# waterius-factory-2_0.net
KiCad netlist of a schematic drawn in EAGLE
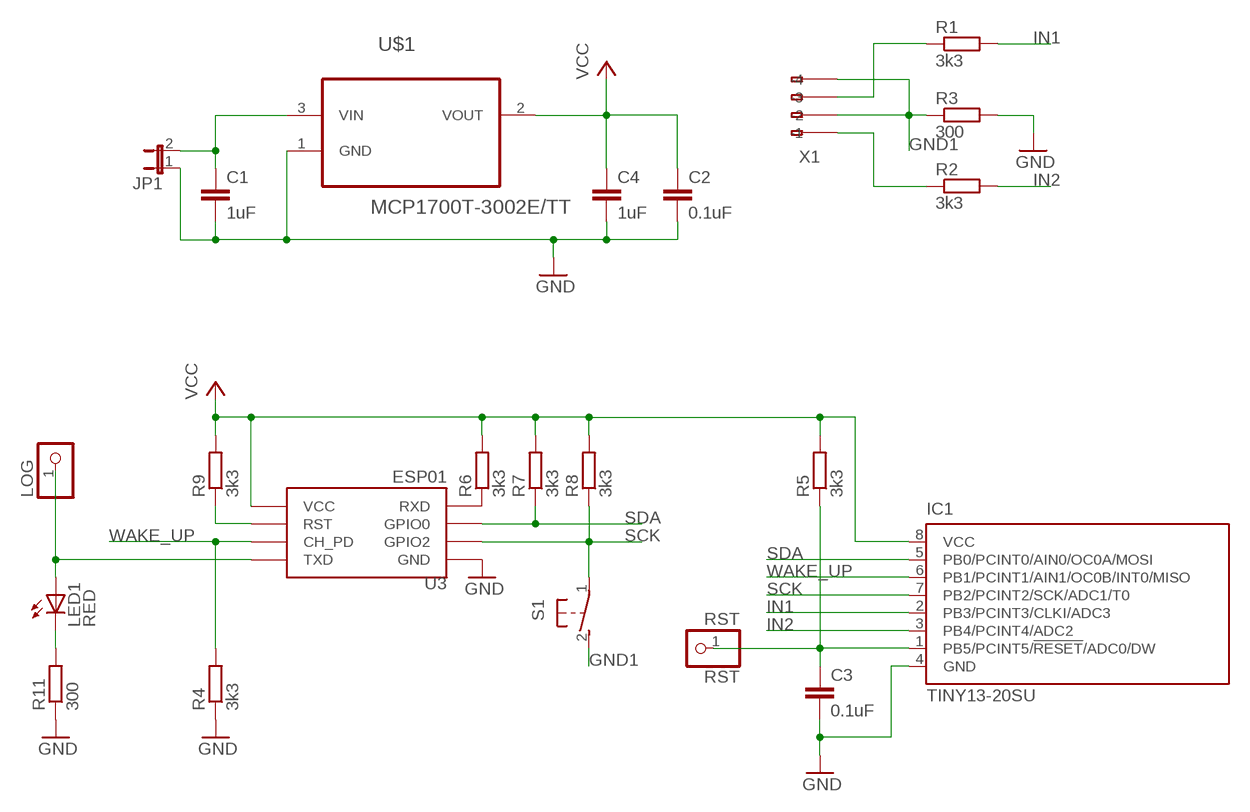
[diagram p0: schematic, sheet 1]

(export (version "E")
  (design (tool "Eeschema 10.0.6"))
  (components
    (comp (ref "C1")
      (value "1uF")
      (footprint "eagle-import:C0805")
      (libsource (lib "eagle-import") (part "C-EUC0805"))
    )
    (comp (ref "C2")
      (value "0.1uF")
      (footprint "eagle-import:C0805")
      (libsource (lib "eagle-import") (part "C-EUC0805"))
    )
    (comp (ref "C3")
      (value "0.1uF")
      (footprint "eagle-import:C0805")
      (libsource (lib "eagle-import") (part "C-EUC0805"))
    )
    (comp (ref "C4")
      (value "1uF")
      (footprint "eagle-import:C0805")
      (libsource (lib "eagle-import") (part "C-EUC0805"))
    )
    (comp (ref "IC1")
      (value "TINY13-20SU")
      (footprint "eagle-import:8S2")
      (fields (field (name "MPN") "ATTINY13-20SU"))
      (libsource (lib "eagle-import") (part "TINY13SU-20"))
    )
    (comp (ref "JP1")
      (value "JP1E")
      (footprint "eagle-import:JP1")
      (libsource (lib "eagle-import") (part "JP1E"))
    )
    (comp (ref "LED1")
      (value "RED")
      (footprint "eagle-import:LED3MM")
      (libsource (lib "eagle-import") (part "LED3MM"))
    )
    (comp (ref "LOG")
      (value "PINHD-1X1")
      (footprint "eagle-import:1X01")
      (libsource (lib "eagle-import") (part "PINHD-1X1"))
    )
    (comp (ref "R1")
      (value "3k3")
      (footprint "eagle-import:R0805")
      (libsource (lib "eagle-import") (part "R-EU_R0805"))
    )
    (comp (ref "R2")
      (value "3k3")
      (footprint "eagle-import:R0805")
      (libsource (lib "eagle-import") (part "R-EU_R0805"))
    )
    (comp (ref "R3")
      (value "300")
      (footprint "eagle-import:R0805")
      (libsource (lib "eagle-import") (part "R-EU_R0805"))
    )
    (comp (ref "R4")
      (value "3k3")
      (footprint "eagle-import:R0805")
      (libsource (lib "eagle-import") (part "R-EU_R0805"))
    )
    (comp (ref "R5")
      (value "3k3")
      (footprint "eagle-import:R0805")
      (libsource (lib "eagle-import") (part "R-EU_R0805"))
    )
    (comp (ref "R6")
      (value "3k3")
      (footprint "eagle-import:R0805")
      (libsource (lib "eagle-import") (part "R-EU_R0805"))
    )
    (comp (ref "R7")
      (value "3k3")
      (footprint "eagle-import:R0805")
      (libsource (lib "eagle-import") (part "R-EU_R0805"))
    )
    (comp (ref "R8")
      (value "3k3")
      (footprint "eagle-import:R0805")
      (libsource (lib "eagle-import") (part "R-EU_R0805"))
    )
    (comp (ref "R9")
      (value "3k3")
      (footprint "eagle-import:R0805")
      (libsource (lib "eagle-import") (part "R-EU_R0805"))
    )
    (comp (ref "R11")
      (value "300")
      (footprint "eagle-import:R0805")
      (libsource (lib "eagle-import") (part "R-EU_R0805"))
    )
    (comp (ref "RST")
      (value "RST")
      (footprint "eagle-import:1X01")
      (libsource (lib "eagle-import") (part "PINHD-1X1"))
    )
    (comp (ref "S1")
      (value "31-XX")
      (footprint "eagle-import:B3F-31XX")
      (fields (field (name "MPN") "B3F-3100"))
      (libsource (lib "eagle-import") (part "31-XX"))
    )
    (comp (ref "U$1")
      (value "MCP1700T-3002E/TT")
      (footprint "eagle-import:SOT95P237X112-3N")
      (fields (field (name "MF") "Microchip"))
      (libsource (lib "eagle-import") (part "MCP1700T-3002E/TT"))
    )
    (comp (ref "U3")
      (value "ESP01")
      (footprint "eagle-import:ESP01")
      (libsource (lib "eagle-import") (part "ESP01"))
    )
    (comp (ref "X1")
      (value "233-104")
      (footprint "eagle-import:233-104")
      (libsource (lib "eagle-import") (part "233-104"))
    )
  )
  (nets
    (net (code "1") (name "/GND1") (class "Default")
      (node (ref "R3") (pin "1") (pinfunction "1_1") (pintype "passive"))
      (node (ref "S1") (pin "2") (pinfunction "S_2") (pintype "passive"))
      (node (ref "X1") (pin "A2") (pinfunction "-2_A2") (pintype "passive"))
      (node (ref "X1") (pin "A4") (pinfunction "-4_A4") (pintype "passive"))
    )
    (net (code "2") (name "/IN1") (class "Default")
      (node (ref "IC1") (pin "2") (pinfunction "PB3/PCINT3/CLKI/ADC3_2") (pintype "bidirectional"))
      (node (ref "R1") (pin "2") (pinfunction "2_2") (pintype "passive"))
    )
    (net (code "3") (name "/IN2") (class "Default")
      (node (ref "IC1") (pin "3") (pinfunction "PB4/PCINT4/ADC2_3") (pintype "bidirectional"))
      (node (ref "R2") (pin "2") (pinfunction "2_2") (pintype "passive"))
    )
    (net (code "4") (name "/SCK") (class "Default")
      (node (ref "IC1") (pin "7") (pinfunction "PB2/PCINT2/SCK/ADC1/T0_7") (pintype "bidirectional"))
      (node (ref "R8") (pin "1") (pinfunction "1_1") (pintype "passive"))
      (node (ref "S1") (pin "1") (pinfunction "P_1") (pintype "passive"))
      (node (ref "U3") (pin "GPIO2") (pinfunction "GPIO2_GPIO2") (pintype "bidirectional"))
    )
    (net (code "5") (name "/SDA") (class "Default")
      (node (ref "IC1") (pin "5") (pinfunction "PB0/PCINT0/AIN0/OC0A/MOSI_5") (pintype "bidirectional"))
      (node (ref "R7") (pin "1") (pinfunction "1_1") (pintype "passive"))
      (node (ref "U3") (pin "GPIO0") (pinfunction "GPIO0_GPIO0") (pintype "bidirectional"))
    )
    (net (code "6") (name "/WAKE_UP") (class "Default")
      (node (ref "IC1") (pin "6") (pinfunction "PB1/PCINT1/AIN1/OC0B/INT0/MISO_6") (pintype "bidirectional"))
      (node (ref "R4") (pin "2") (pinfunction "2_2") (pintype "passive"))
      (node (ref "U3") (pin "CH_PD") (pinfunction "CH_PD_CH_PD") (pintype "bidirectional"))
    )
    (net (code "7") (name "GND") (class "Default")
      (node (ref "C1") (pin "2") (pinfunction "2_2") (pintype "passive"))
      (node (ref "C2") (pin "2") (pinfunction "2_2") (pintype "passive"))
      (node (ref "C3") (pin "2") (pinfunction "2_2") (pintype "passive"))
      (node (ref "C4") (pin "2") (pinfunction "2_2") (pintype "passive"))
      (node (ref "IC1") (pin "4") (pinfunction "GND_4") (pintype "power_in"))
      (node (ref "JP1") (pin "1") (pinfunction "1_1") (pintype "passive"))
      (node (ref "R11") (pin "1") (pinfunction "1_1") (pintype "passive"))
      (node (ref "R3") (pin "2") (pinfunction "2_2") (pintype "passive"))
      (node (ref "R4") (pin "1") (pinfunction "1_1") (pintype "passive"))
      (node (ref "U$1") (pin "1") (pinfunction "GND_1") (pintype "passive"))
      (node (ref "U3") (pin "GND") (pinfunction "GND_GND") (pintype "bidirectional"))
    )
    (net (code "8") (name "Net-(IC1-PB5{slash}PCINT5{slash}~{RESET}{slash}ADC0{slash}DW)") (class "Default")
      (node (ref "C3") (pin "1") (pinfunction "1_1") (pintype "passive"))
      (node (ref "IC1") (pin "1") (pinfunction "PB5/PCINT5/~{RESET}/ADC0/DW_1") (pintype "bidirectional"))
      (node (ref "R5") (pin "1") (pinfunction "1_1") (pintype "passive"))
      (node (ref "RST") (pin "1") (pinfunction "1_1") (pintype "passive"))
    )
    (net (code "9") (name "Net-(LED1-C)") (class "Default")
      (node (ref "LED1") (pin "K") (pinfunction "C_K") (pintype "passive"))
      (node (ref "R11") (pin "2") (pinfunction "2_2") (pintype "passive"))
    )
    (net (code "10") (name "Net-(R9-Pad1)") (class "Default")
      (node (ref "R9") (pin "1") (pinfunction "1_1") (pintype "passive"))
      (node (ref "U3") (pin "RST") (pinfunction "RST_RST") (pintype "bidirectional"))
    )
    (net (code "11") (name "Net-(U$1-VIN)") (class "Default")
      (node (ref "C1") (pin "1") (pinfunction "1_1") (pintype "passive"))
      (node (ref "JP1") (pin "2") (pinfunction "2_2") (pintype "passive"))
      (node (ref "U$1") (pin "3") (pinfunction "VIN_3") (pintype "input"))
    )
    (net (code "12") (name "Net-(U3-RXD)") (class "Default")
      (node (ref "R6") (pin "1") (pinfunction "1_1") (pintype "passive"))
      (node (ref "U3") (pin "RX") (pinfunction "RXD_RX") (pintype "bidirectional"))
    )
    (net (code "13") (name "Net-(U3-TXD)") (class "Default")
      (node (ref "LED1") (pin "A") (pinfunction "A_A") (pintype "passive"))
      (node (ref "LOG") (pin "1") (pinfunction "1_1") (pintype "passive"))
      (node (ref "U3") (pin "TX") (pinfunction "TXD_TX") (pintype "bidirectional"))
    )
    (net (code "14") (name "Net-(X1--1)") (class "Default")
      (node (ref "R2") (pin "1") (pinfunction "1_1") (pintype "passive"))
      (node (ref "X1") (pin "A1") (pinfunction "-1_A1") (pintype "passive"))
    )
    (net (code "15") (name "Net-(X1--3)") (class "Default")
      (node (ref "R1") (pin "1") (pinfunction "1_1") (pintype "passive"))
      (node (ref "X1") (pin "A3") (pinfunction "-3_A3") (pintype "passive"))
    )
    (net (code "16") (name "VCC") (class "Default")
      (node (ref "C2") (pin "1") (pinfunction "1_1") (pintype "passive"))
      (node (ref "C4") (pin "1") (pinfunction "1_1") (pintype "passive"))
      (node (ref "IC1") (pin "8") (pinfunction "VCC_8") (pintype "power_in"))
      (node (ref "R5") (pin "2") (pinfunction "2_2") (pintype "passive"))
      (node (ref "R6") (pin "2") (pinfunction "2_2") (pintype "passive"))
      (node (ref "R7") (pin "2") (pinfunction "2_2") (pintype "passive"))
      (node (ref "R8") (pin "2") (pinfunction "2_2") (pintype "passive"))
      (node (ref "R9") (pin "2") (pinfunction "2_2") (pintype "passive"))
      (node (ref "U$1") (pin "2") (pinfunction "VOUT_2") (pintype "output"))
      (node (ref "U3") (pin "VCC") (pinfunction "VCC_VCC") (pintype "bidirectional"))
    )
    (net (code "17") (name "unconnected-(X1-B-1-PadB1)") (class "Default")
      (node (ref "X1") (pin "B1") (pinfunction "B-1_B1") (pintype "passive"))
    )
    (net (code "18") (name "unconnected-(X1-B-2-PadB2)") (class "Default")
      (node (ref "X1") (pin "B2") (pinfunction "B-2_B2") (pintype "passive"))
    )
    (net (code "19") (name "unconnected-(X1-B-3-PadB3)") (class "Default")
      (node (ref "X1") (pin "B3") (pinfunction "B-3_B3") (pintype "passive"))
    )
    (net (code "20") (name "unconnected-(X1-B-4-PadB4)") (class "Default")
      (node (ref "X1") (pin "B4") (pinfunction "B-4_B4") (pintype "passive"))
    )
  )
)
